# IMU_NoPilot.net
KiCad netlist of a schematic drawn in EAGLE
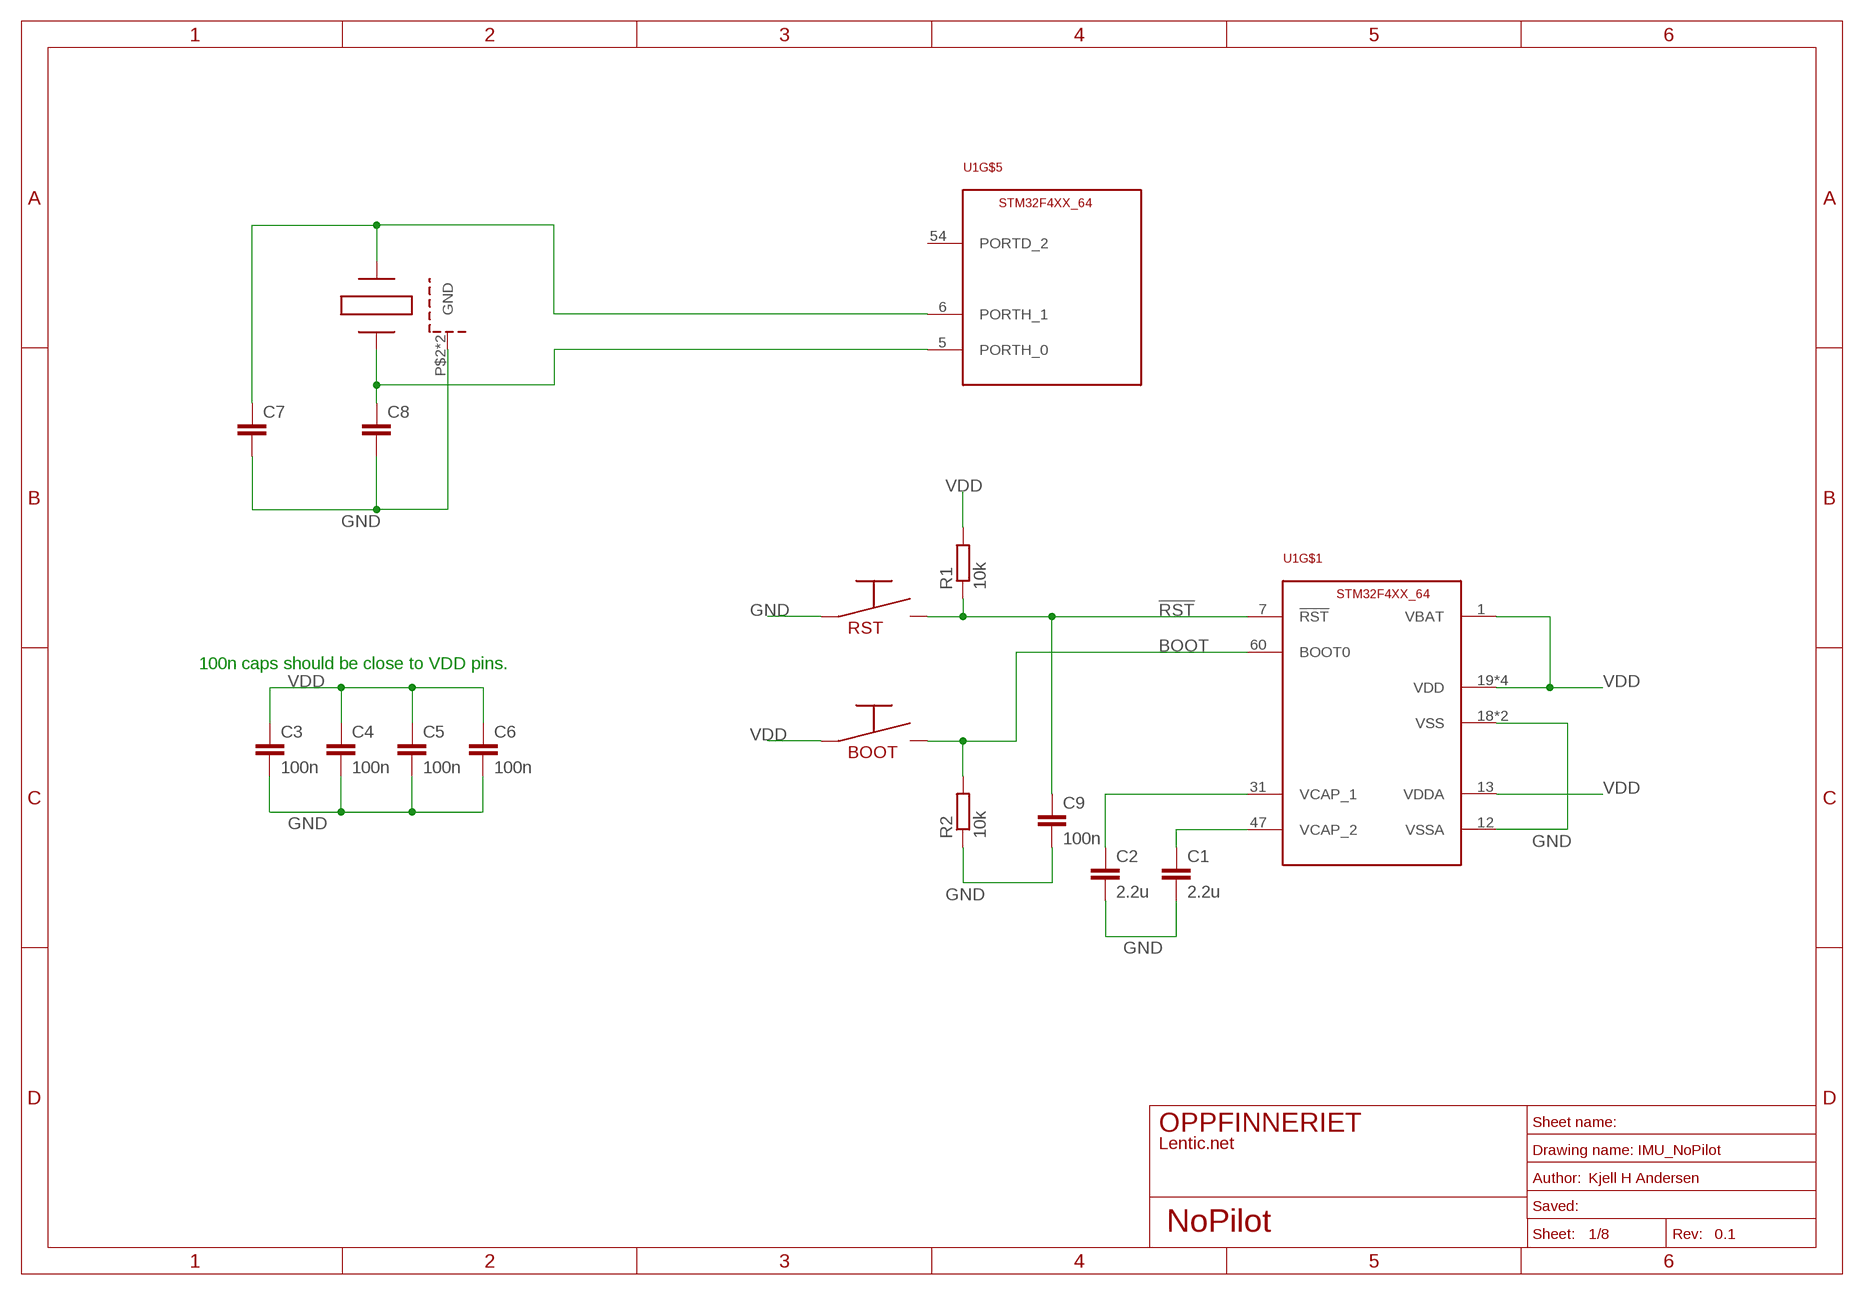
[diagram p0: schematic, sheet 1]
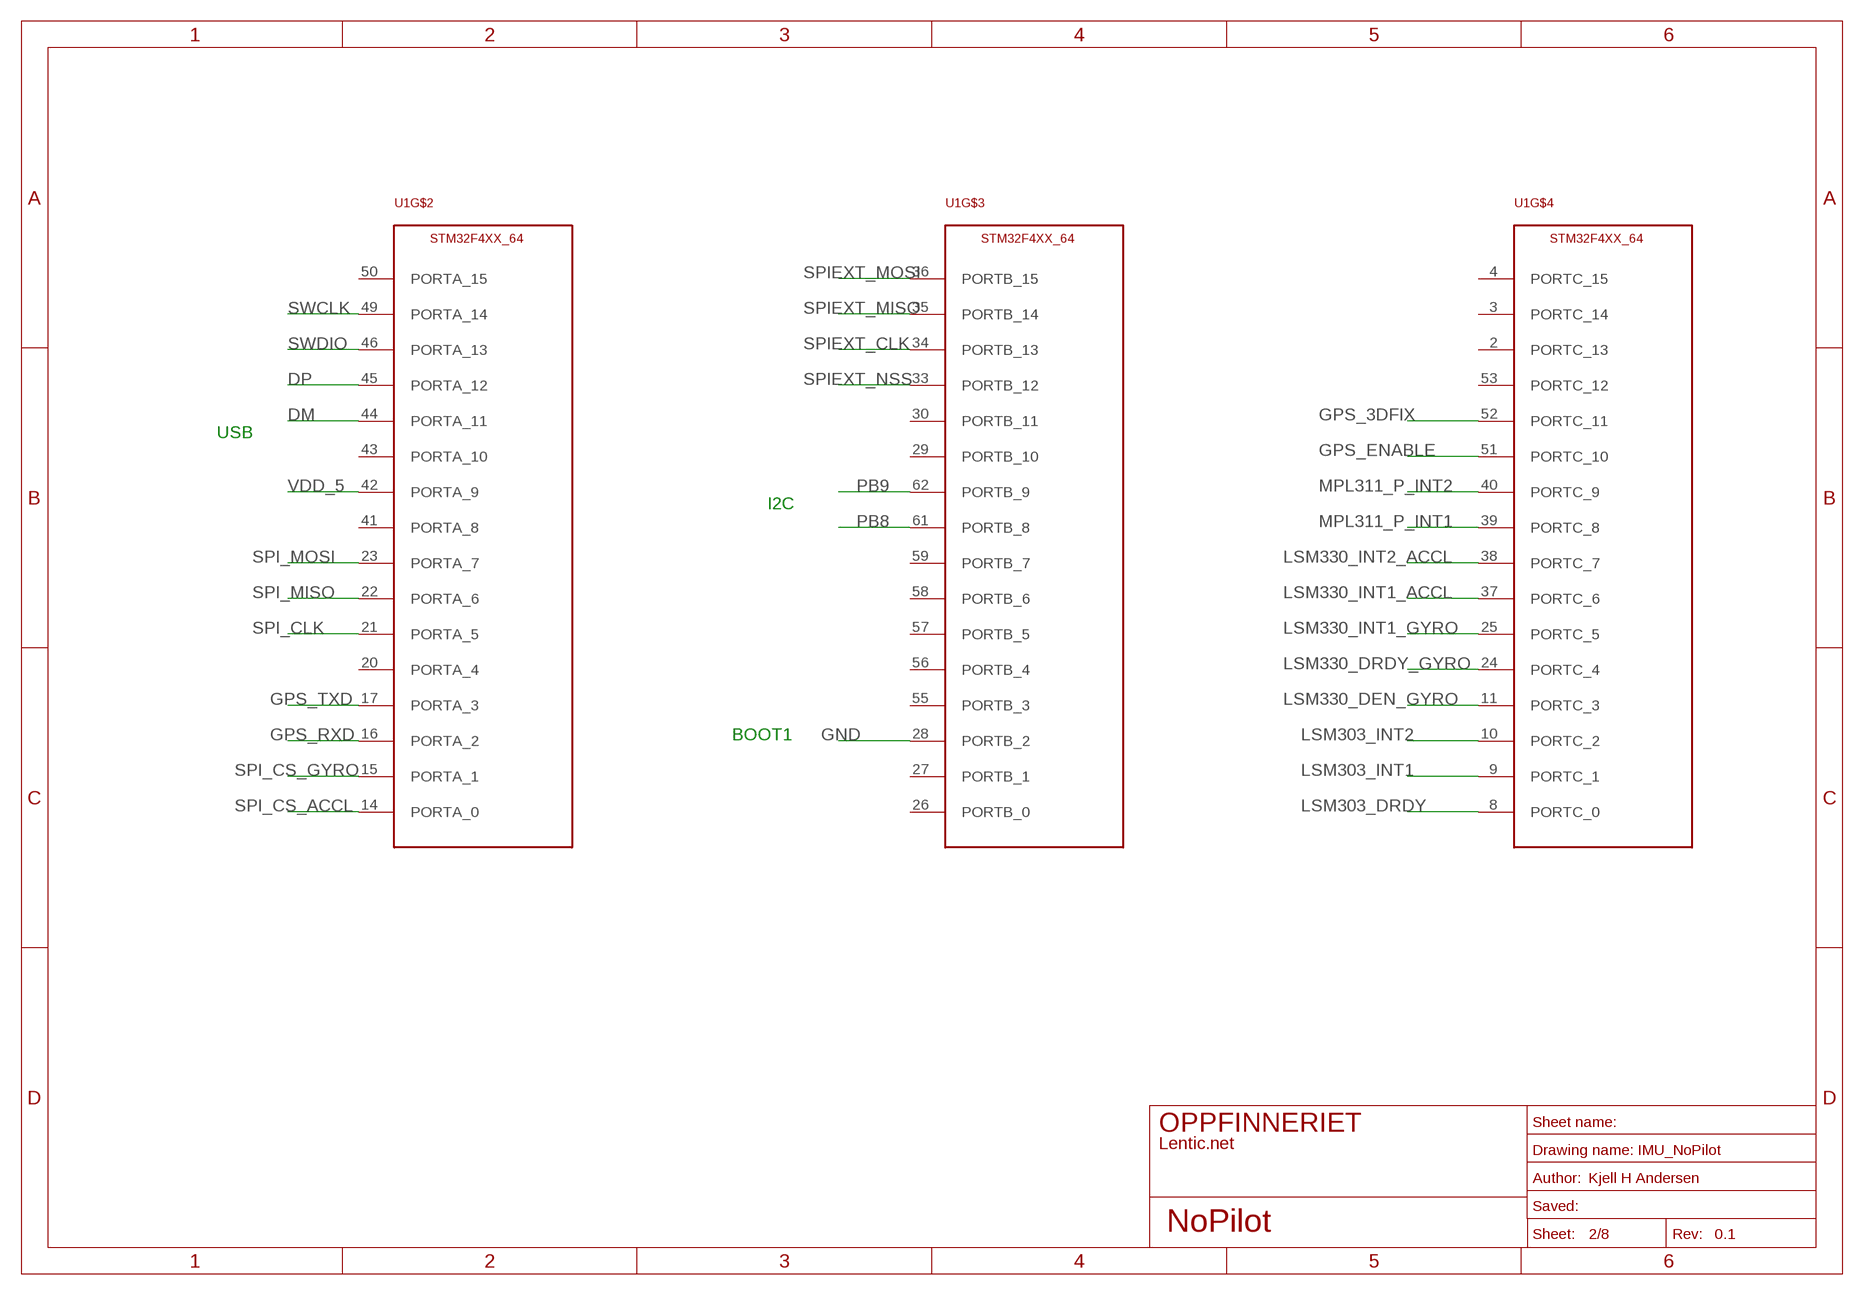
[diagram p1: schematic, sheet 2]
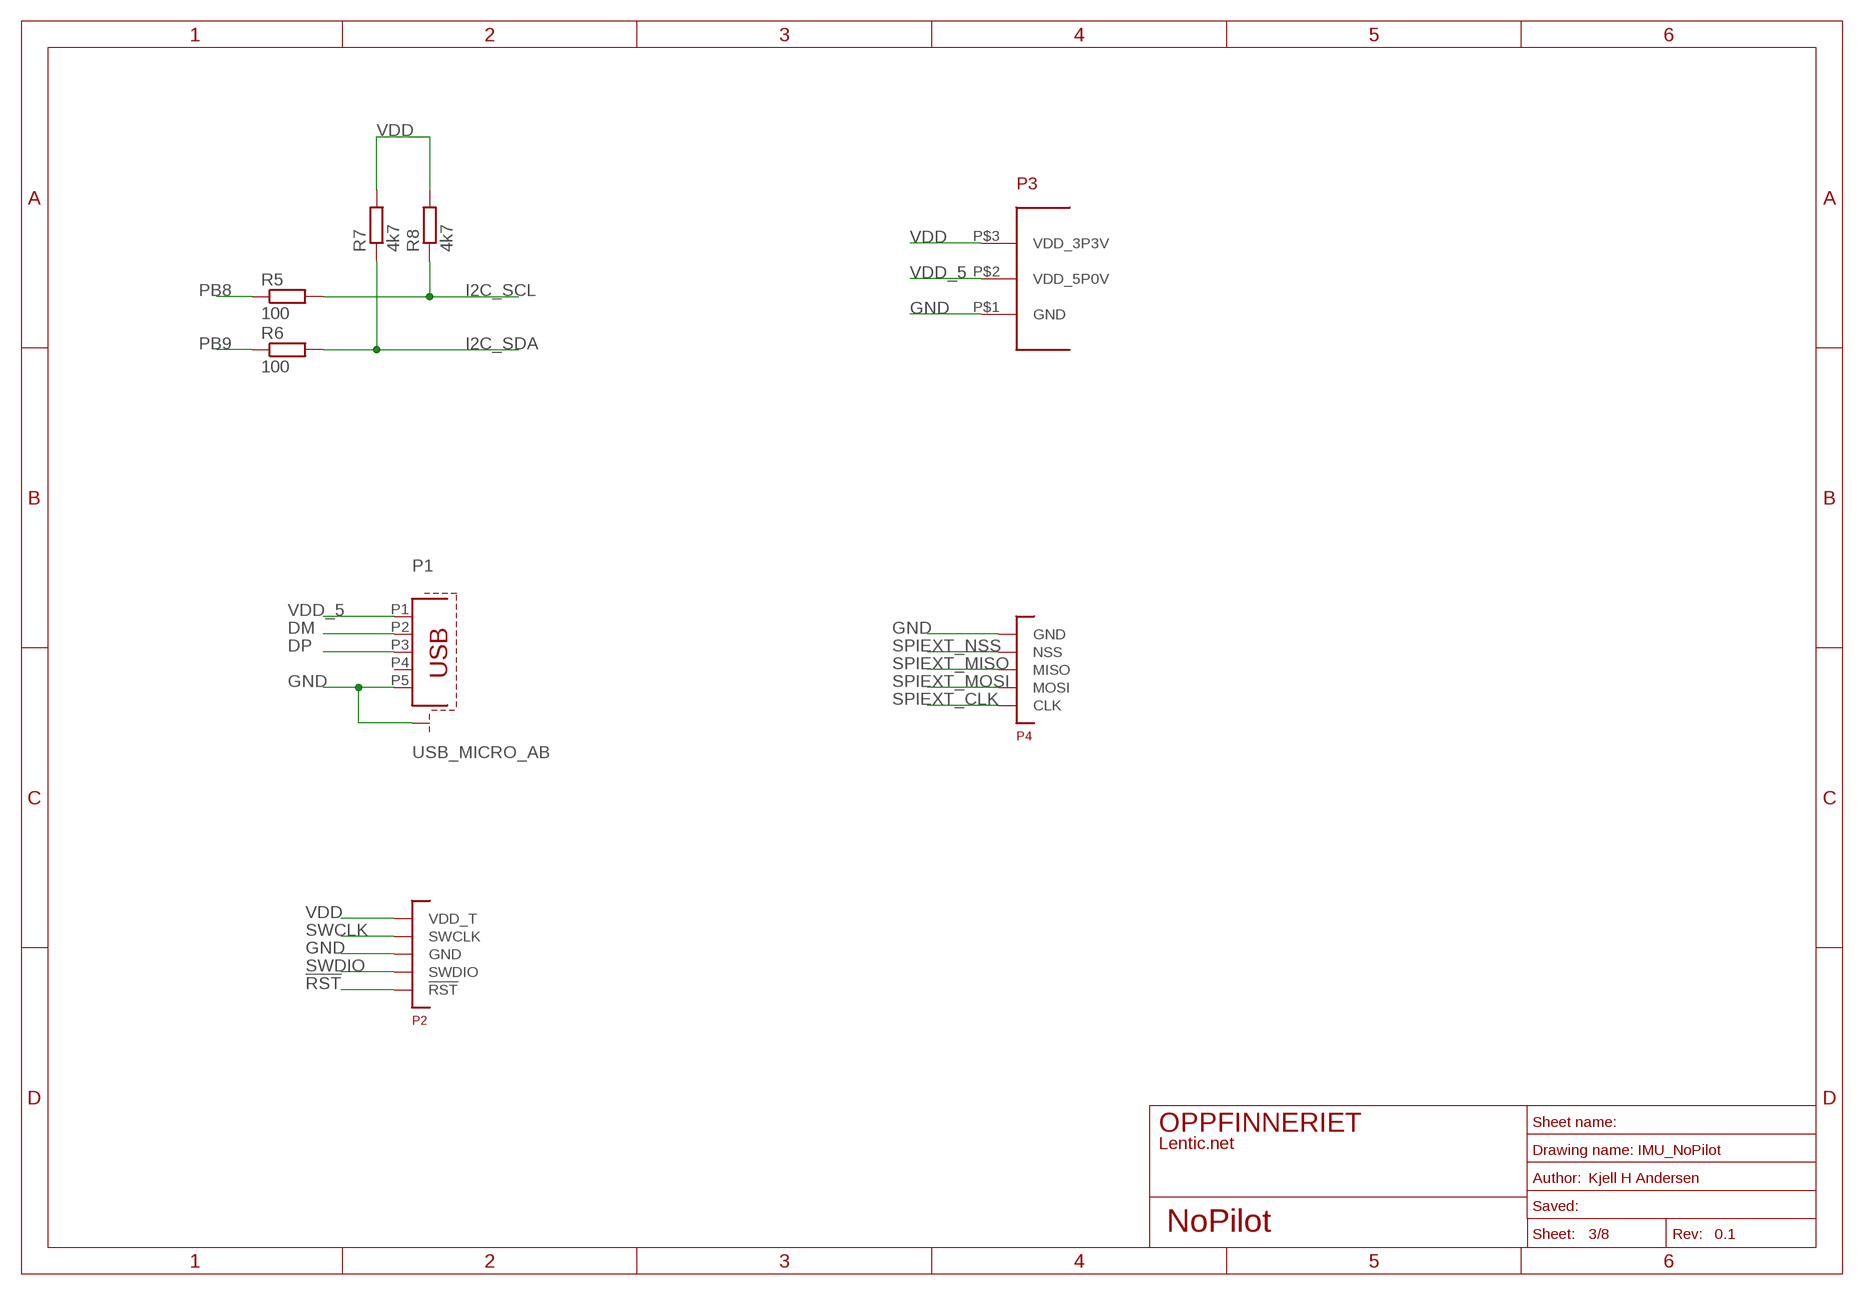
[diagram p2: schematic, sheet 3]
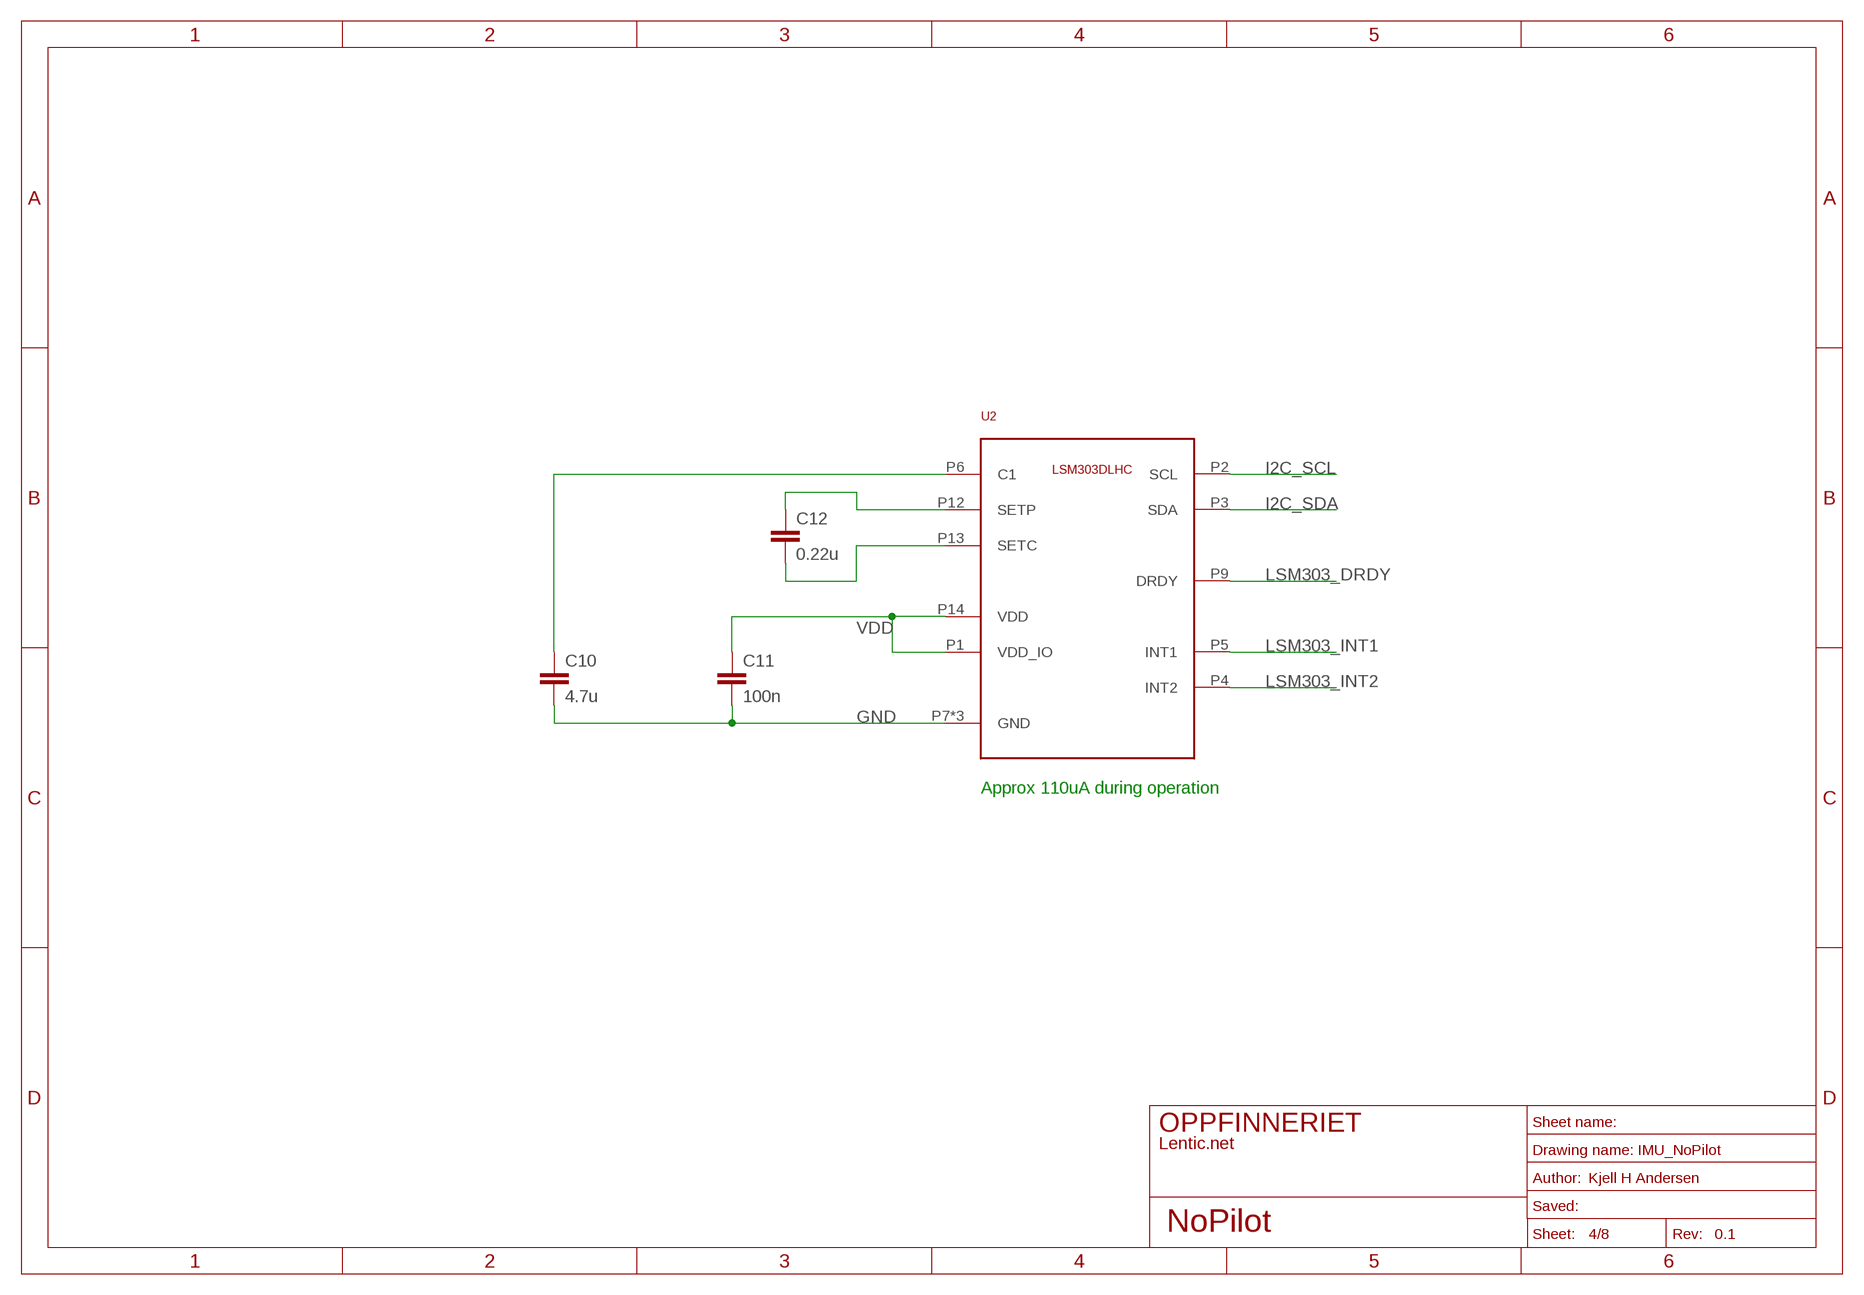
[diagram p3: schematic, sheet 4]
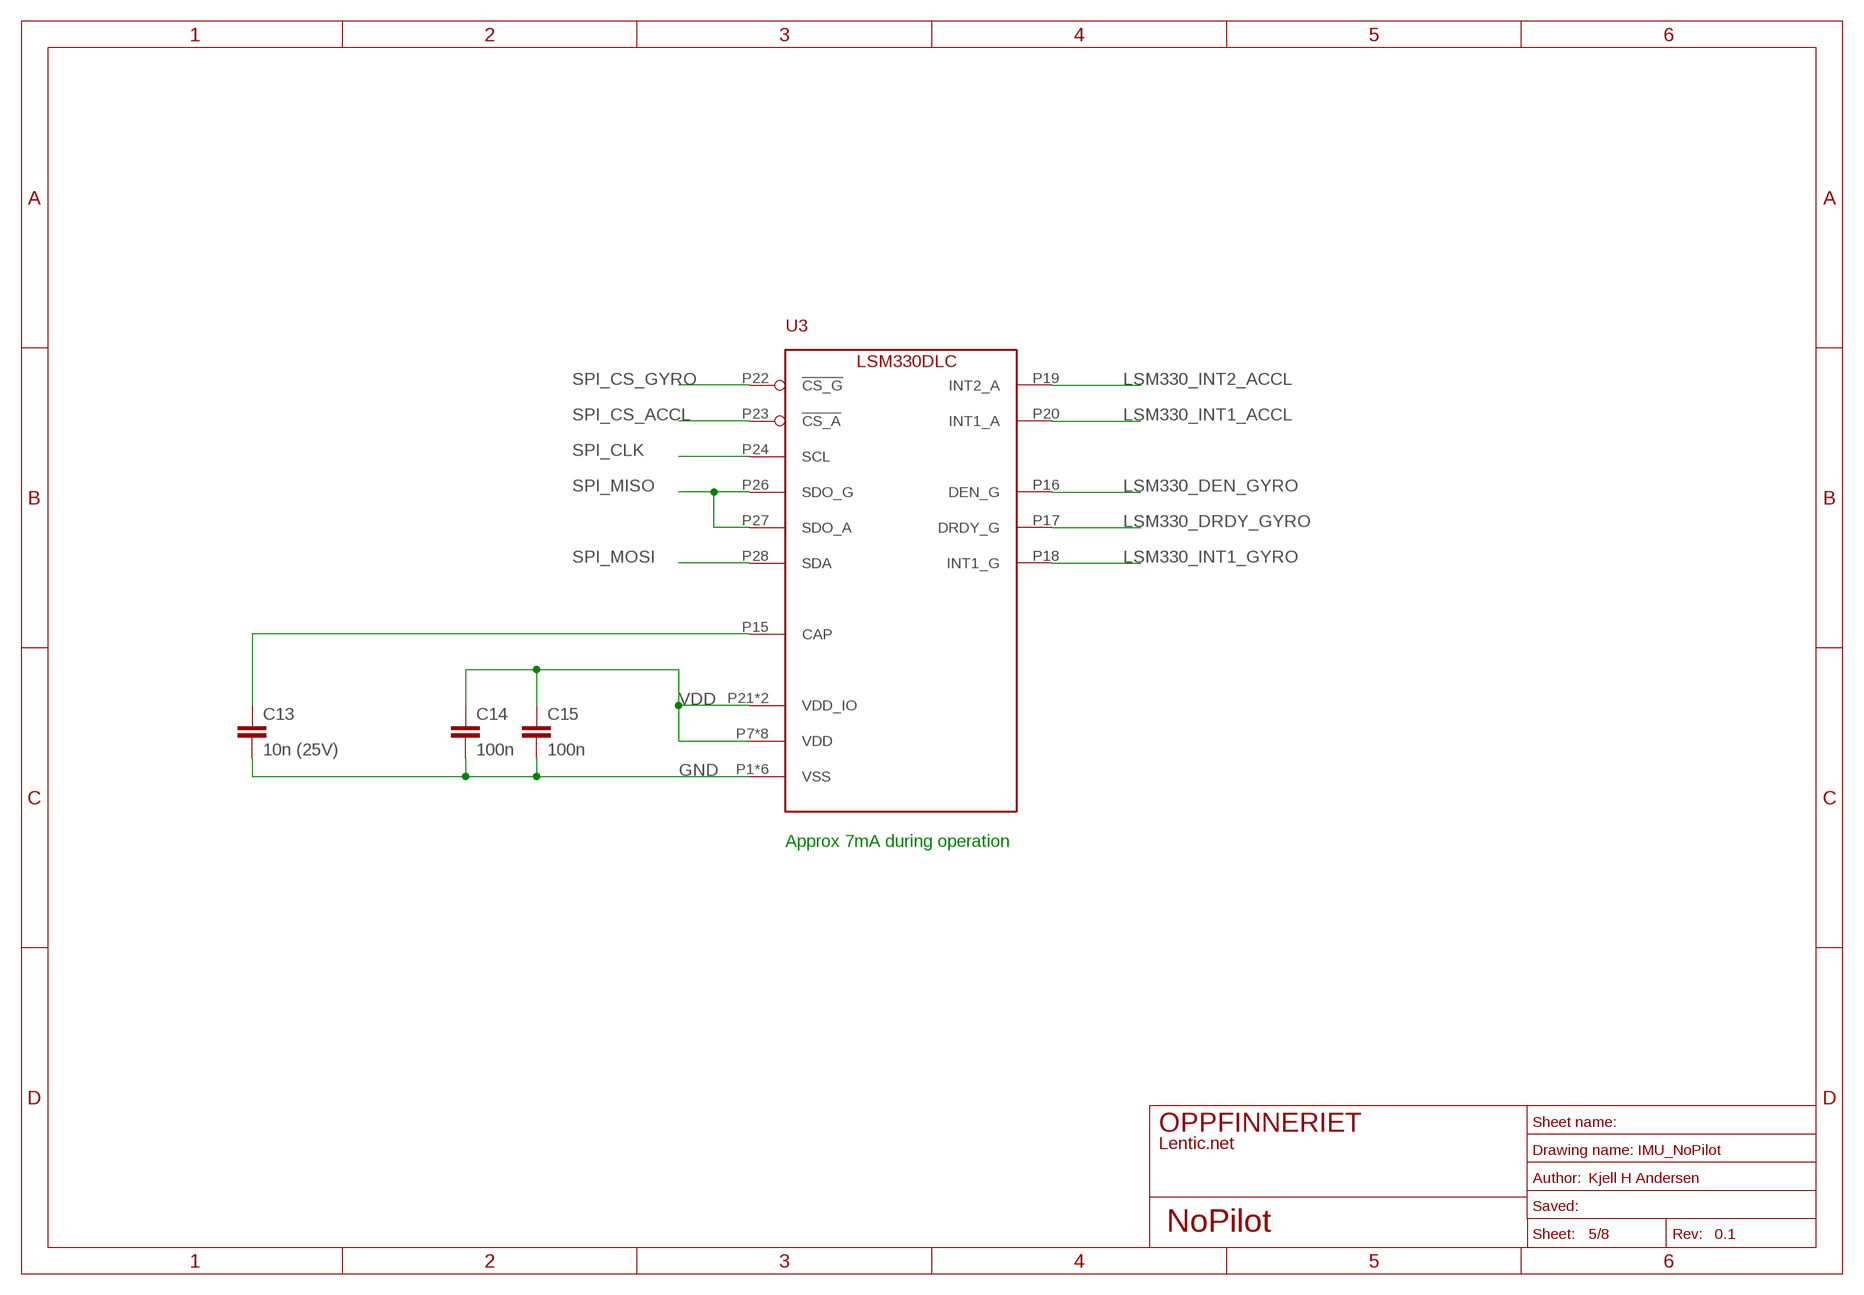
[diagram p4: schematic, sheet 5]
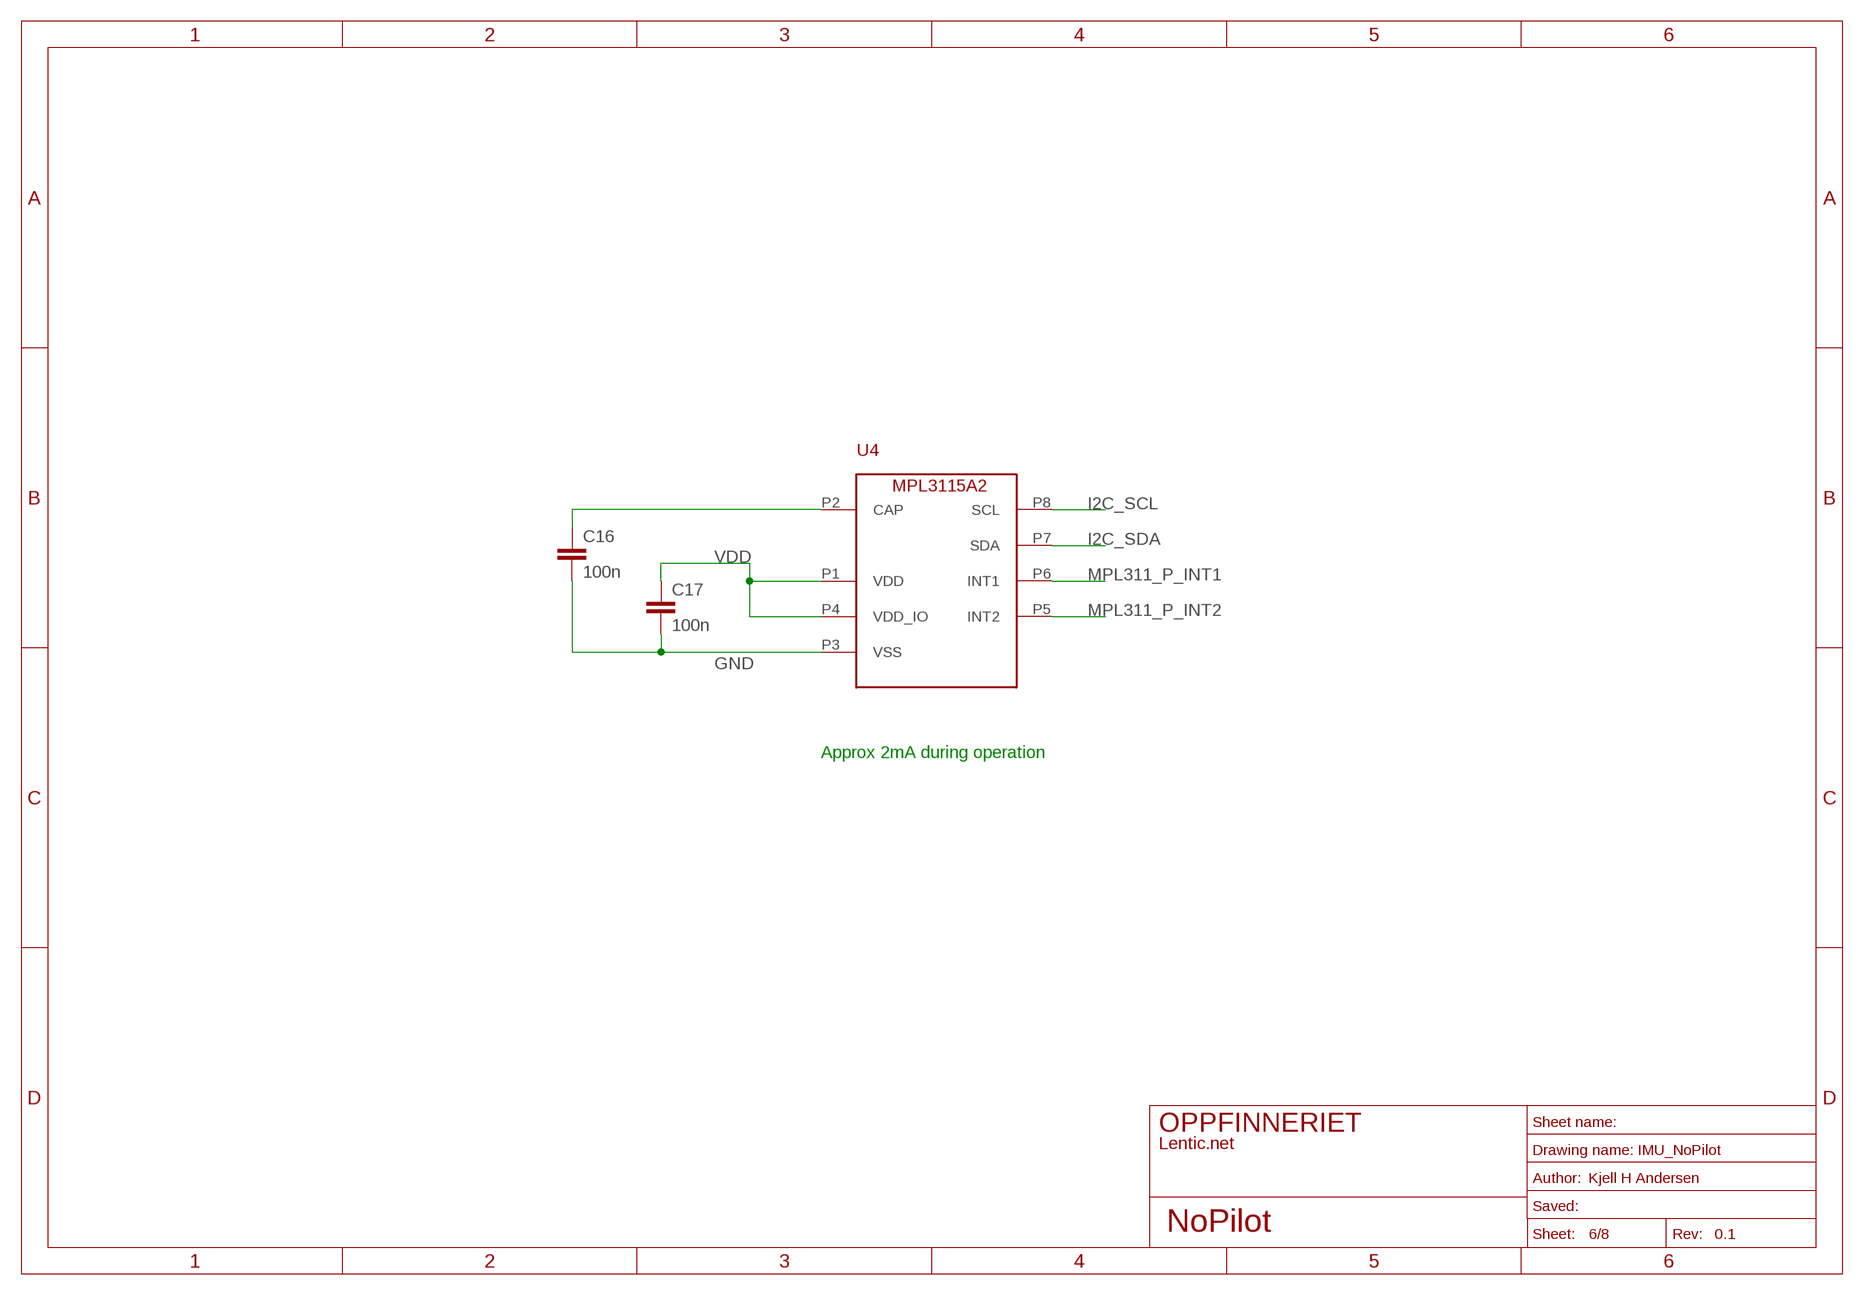
[diagram p5: schematic, sheet 6]
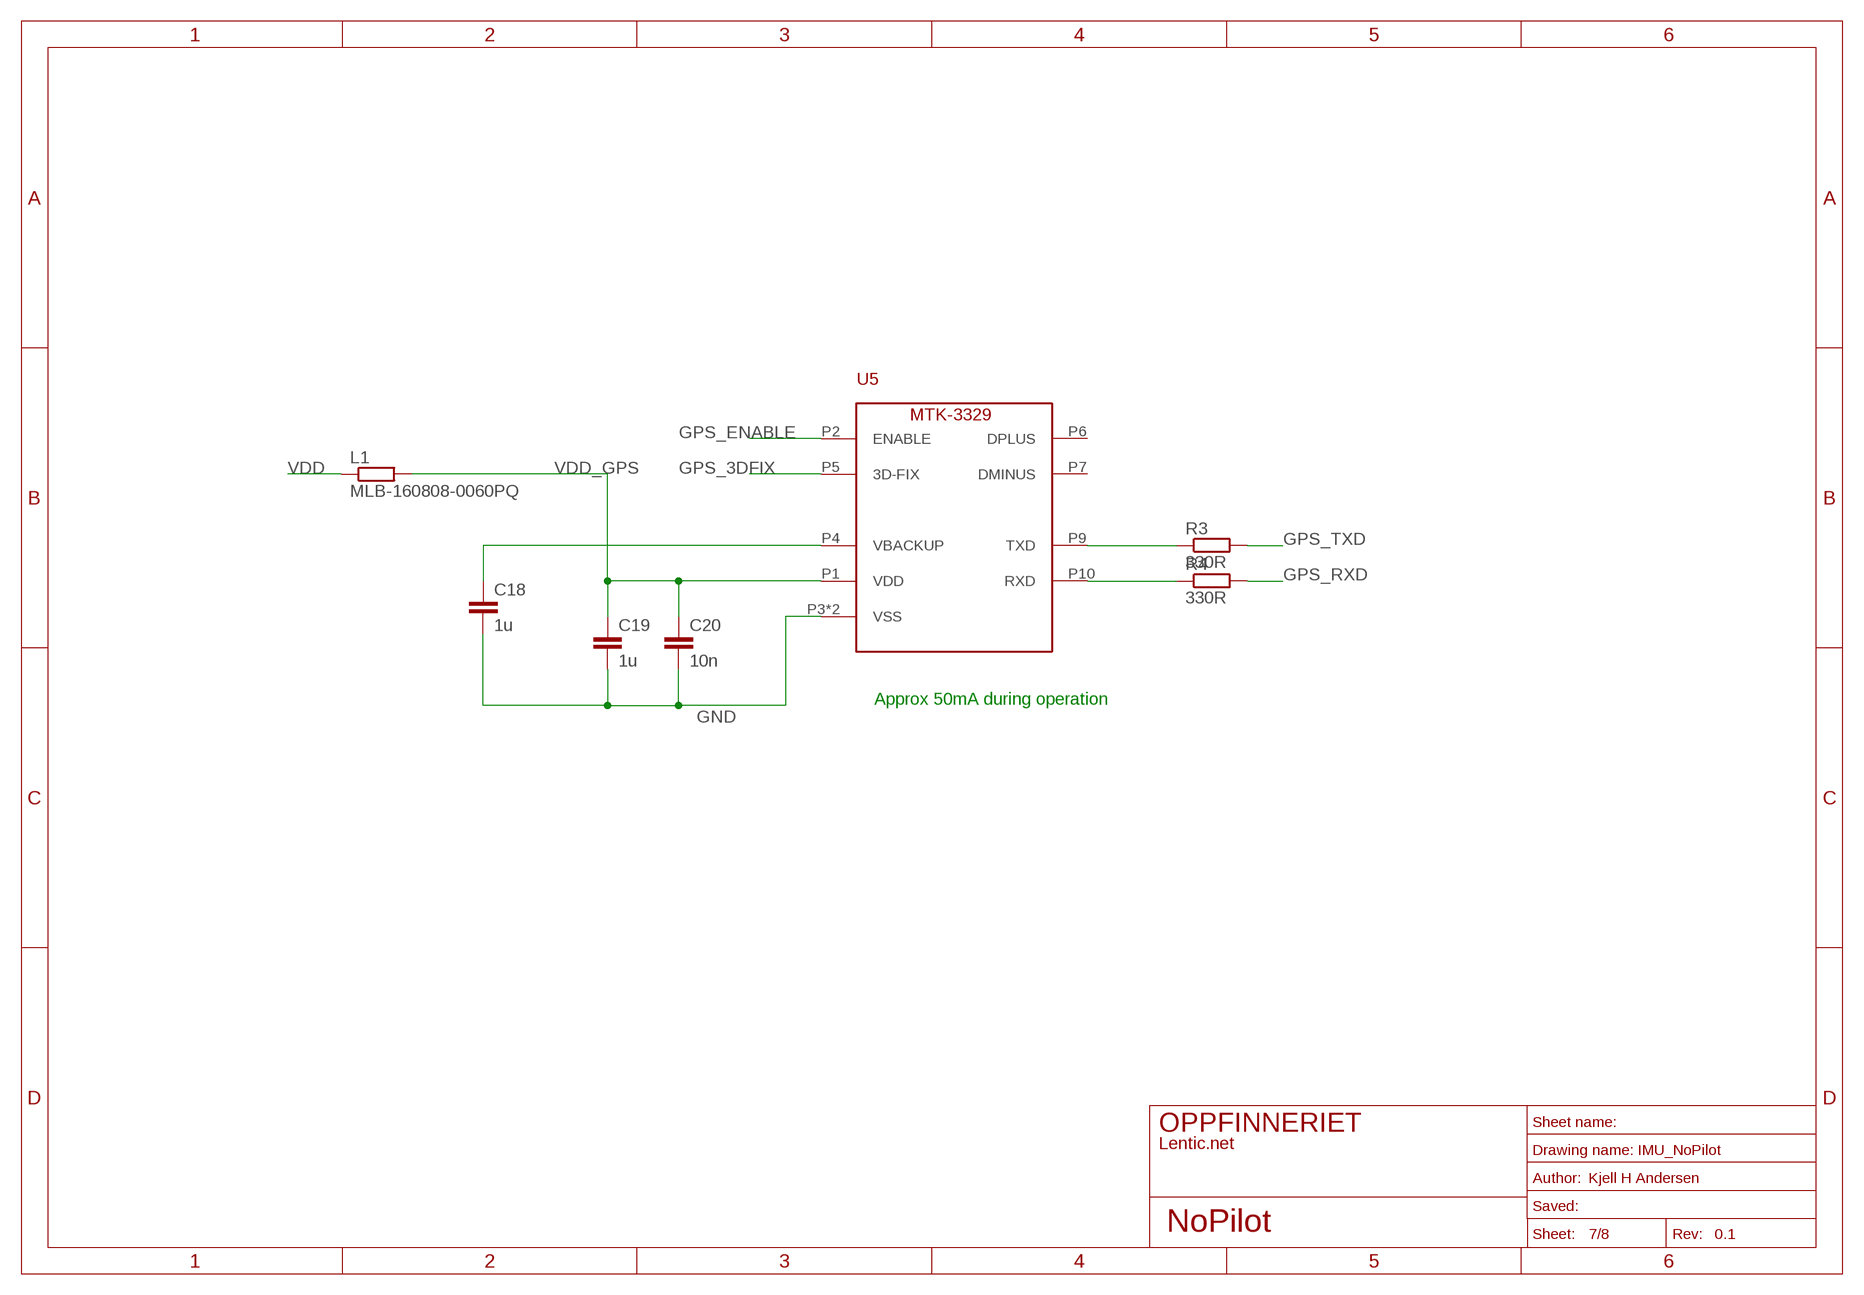
[diagram p6: schematic, sheet 7]
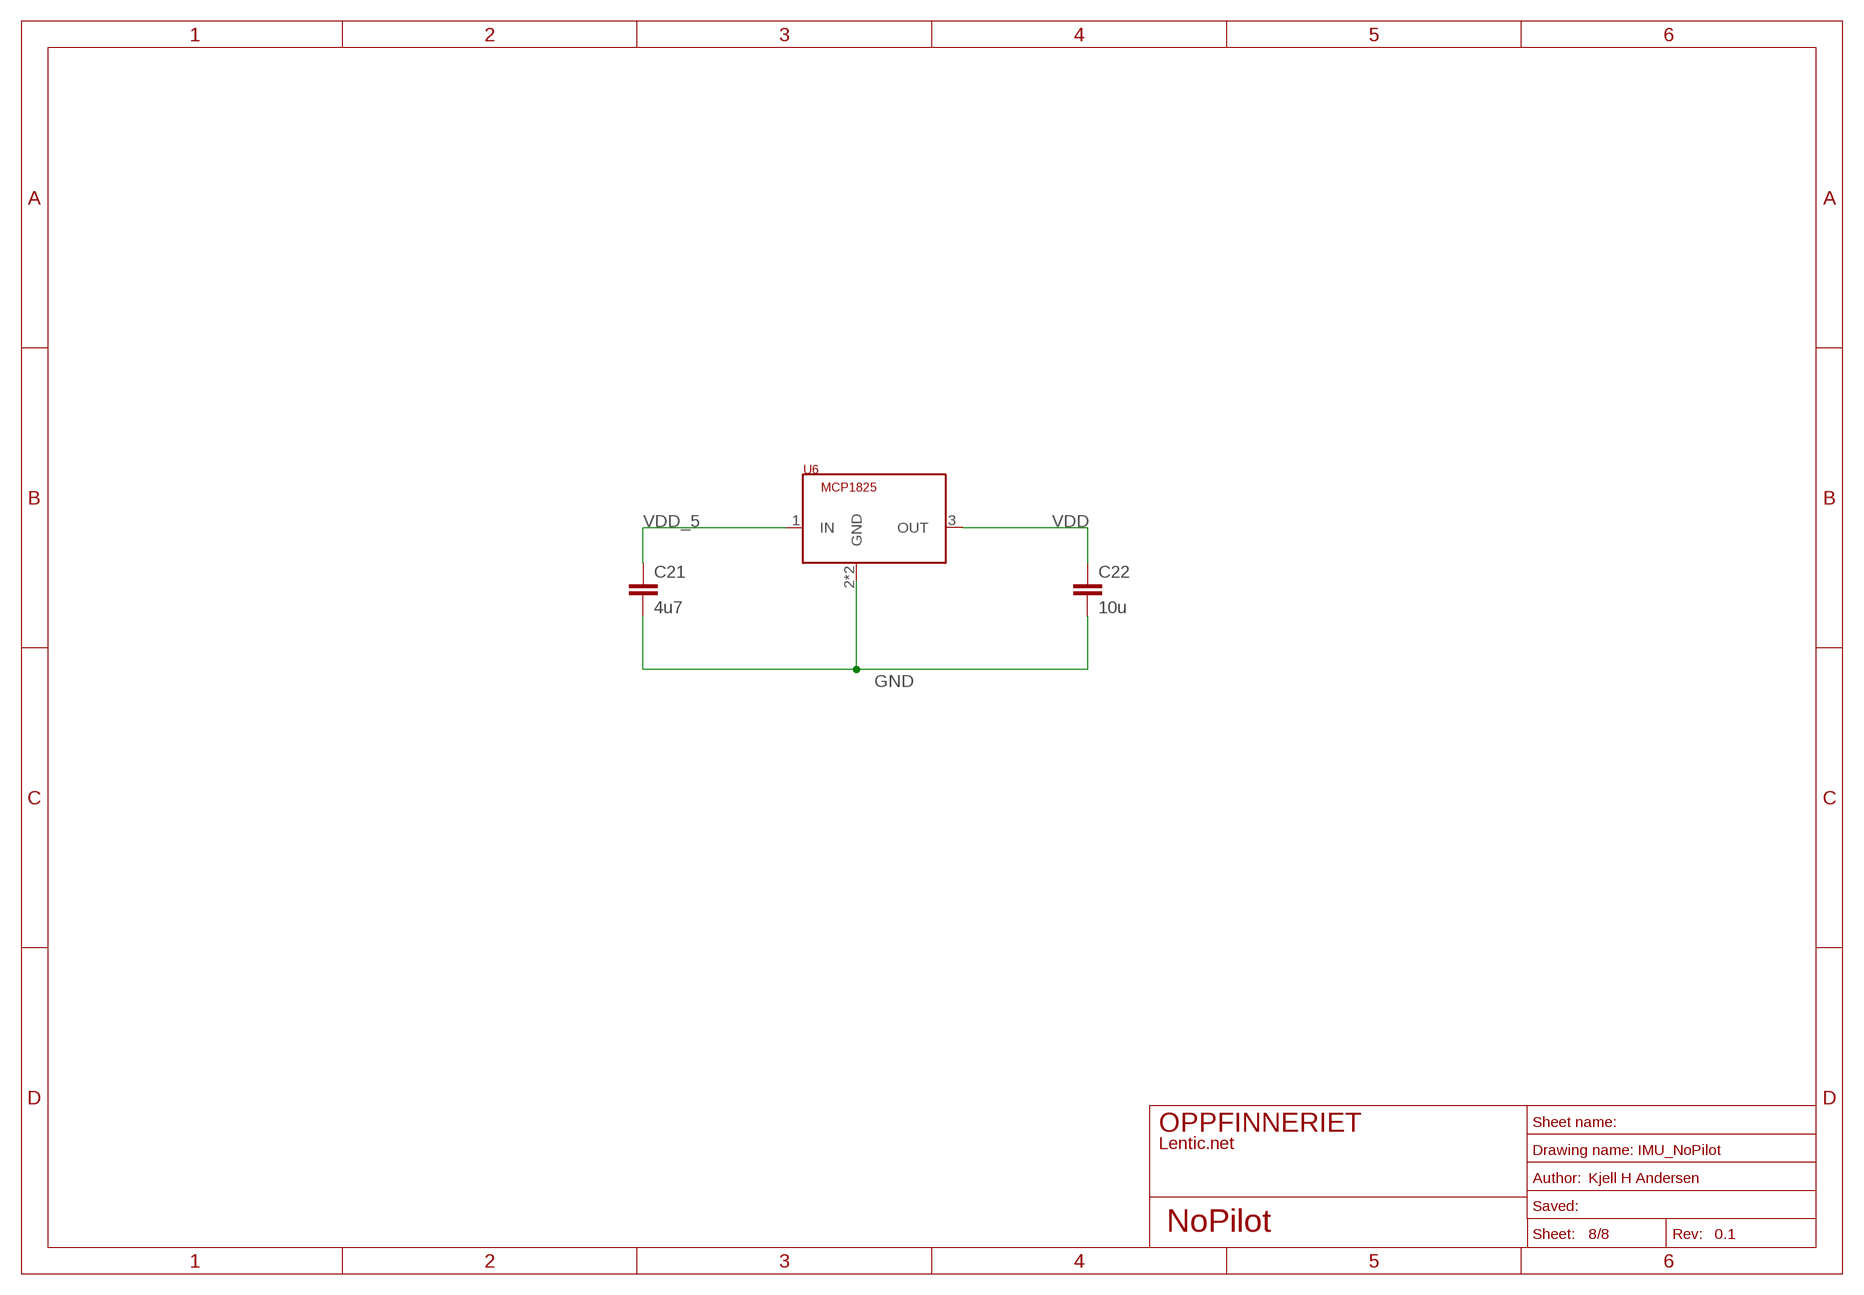
[diagram p7: schematic, sheet 8]

(export (version "E")
  (design (tool "Eeschema 10.0.6"))
  (components
    (comp (ref "C10")
      (value "4.7u")
      (footprint "eagle-import:C0805")
      (libsource (lib "eagle-import") (part "C-EUC0805"))
    )
    (comp (ref "C11")
      (value "100n")
      (footprint "eagle-import:C0402")
      (libsource (lib "eagle-import") (part "C-EUC0402"))
    )
    (comp (ref "C12")
      (value "0.22u")
      (footprint "eagle-import:C0402")
      (libsource (lib "eagle-import") (part "C-EUC0402"))
    )
    (comp (ref "U2")
      (value "LSM303DLHC")
      (footprint "eagle-import:LGA_3X5X1_14L")
      (libsource (lib "eagle-import") (part "LSM303DLHC"))
    )
    (comp (ref "C16")
      (value "100n")
      (footprint "eagle-import:C0402")
      (libsource (lib "eagle-import") (part "C-EUC0402"))
    )
    (comp (ref "C17")
      (value "100n")
      (footprint "eagle-import:C0402")
      (libsource (lib "eagle-import") (part "C-EUC0402"))
    )
    (comp (ref "U4")
      (value "MPL3115A2")
      (footprint "eagle-import:LGA_3X5_8")
      (libsource (lib "eagle-import") (part "MPL3115A2"))
    )
    (comp (ref "C21")
      (value "4u7")
      (footprint "eagle-import:C0805")
      (libsource (lib "eagle-import") (part "C-EUC0805"))
    )
    (comp (ref "C22")
      (value "10u")
      (footprint "eagle-import:C0805")
      (libsource (lib "eagle-import") (part "C-EUC0805"))
    )
    (comp (ref "U6")
      (value "MCP1825")
      (footprint "eagle-import:SOT223")
      (libsource (lib "eagle-import") (part "MCP1825"))
    )
    (comp (ref "P1")
      (value "USB_MICRO_AB")
      (footprint "eagle-import:USB_MICRO_AB")
      (libsource (lib "eagle-import") (part "USB_MICRO_AB"))
    )
    (comp (ref "P2")
      (value "ST_LINK")
      (footprint "eagle-import:ST_LINK")
      (libsource (lib "eagle-import") (part "ST_LINK"))
    )
    (comp (ref "P3")
      (value "PWR3")
      (footprint "eagle-import:PWR3")
      (libsource (lib "eagle-import") (part "PWR3"))
    )
    (comp (ref "P4")
      (value "SPI_EXT")
      (footprint "eagle-import:PINLIST5_2P54")
      (libsource (lib "eagle-import") (part "SPI_EXT"))
    )
    (comp (ref "R5")
      (value "100")
      (footprint "eagle-import:R0402")
      (libsource (lib "eagle-import") (part "R-EU_R0402"))
    )
    (comp (ref "R6")
      (value "100")
      (footprint "eagle-import:R0402")
      (libsource (lib "eagle-import") (part "R-EU_R0402"))
    )
    (comp (ref "R7")
      (value "4k7")
      (footprint "eagle-import:R0402")
      (libsource (lib "eagle-import") (part "R-EU_R0402"))
    )
    (comp (ref "R8")
      (value "4k7")
      (footprint "eagle-import:R0402")
      (libsource (lib "eagle-import") (part "R-EU_R0402"))
    )
    (comp (ref "C18")
      (value "1u")
      (footprint "eagle-import:C0805")
      (libsource (lib "eagle-import") (part "C-EUC0805"))
    )
    (comp (ref "C19")
      (value "1u")
      (footprint "eagle-import:C0805")
      (libsource (lib "eagle-import") (part "C-EUC0805"))
    )
    (comp (ref "C20")
      (value "10n")
      (footprint "eagle-import:C0402")
      (libsource (lib "eagle-import") (part "C-EUC0402"))
    )
    (comp (ref "L1")
      (value "MLB-160808-0060PQ")
      (footprint "eagle-import:R0603")
      (libsource (lib "eagle-import") (part "R-EU_R0603"))
    )
    (comp (ref "R3")
      (value "330R")
      (footprint "eagle-import:R0402")
      (libsource (lib "eagle-import") (part "R-EU_R0402"))
    )
    (comp (ref "R4")
      (value "330R")
      (footprint "eagle-import:R0402")
      (libsource (lib "eagle-import") (part "R-EU_R0402"))
    )
    (comp (ref "U5")
      (value "MTK-3329")
      (footprint "eagle-import:MTK-3329")
      (libsource (lib "eagle-import") (part "MTK-3329"))
    )
    (comp (ref "BOOT")
      (value "OMRON_B3FS_1000")
      (footprint "eagle-import:OMROM_B3FS-1XXX")
      (libsource (lib "eagle-import") (part "OMRON_B3FS_1000"))
    )
    (comp (ref "C1")
      (value "2.2u")
      (footprint "eagle-import:C0805")
      (libsource (lib "eagle-import") (part "C-EUC0805"))
    )
    (comp (ref "C2")
      (value "2.2u")
      (footprint "eagle-import:C0805")
      (libsource (lib "eagle-import") (part "C-EUC0805"))
    )
    (comp (ref "C3")
      (value "100n")
      (footprint "eagle-import:C0402")
      (libsource (lib "eagle-import") (part "C-EUC0402"))
    )
    (comp (ref "C4")
      (value "100n")
      (footprint "eagle-import:C0402")
      (libsource (lib "eagle-import") (part "C-EUC0402"))
    )
    (comp (ref "C5")
      (value "100n")
      (footprint "eagle-import:C0402")
      (libsource (lib "eagle-import") (part "C-EUC0402"))
    )
    (comp (ref "C6")
      (value "100n")
      (footprint "eagle-import:C0402")
      (libsource (lib "eagle-import") (part "C-EUC0402"))
    )
    (comp (ref "C7")
      (value "C-EUC0402")
      (footprint "eagle-import:C0402")
      (libsource (lib "eagle-import") (part "C-EUC0402"))
    )
    (comp (ref "C8")
      (value "C-EUC0402")
      (footprint "eagle-import:C0402")
      (libsource (lib "eagle-import") (part "C-EUC0402"))
    )
    (comp (ref "C9")
      (value "100n")
      (footprint "eagle-import:C0402")
      (libsource (lib "eagle-import") (part "C-EUC0402"))
    )
    (comp (ref "R1")
      (value "10k")
      (footprint "eagle-import:R0402")
      (libsource (lib "eagle-import") (part "R-EU_R0402"))
    )
    (comp (ref "R2")
      (value "10k")
      (footprint "eagle-import:R0402")
      (libsource (lib "eagle-import") (part "R-EU_R0402"))
    )
    (comp (ref "RST")
      (value "OMRON_B3FS_1000")
      (footprint "eagle-import:OMROM_B3FS-1XXX")
      (libsource (lib "eagle-import") (part "OMRON_B3FS_1000"))
    )
    (comp (ref "U1")
      (value "STM32F4XX_64")
      (footprint "eagle-import:TQFP64")
      (libsource (lib "eagle-import") (part "STM32F4XX_64"))
    )
    (comp (ref "XTAL1")
      (value "XTAL_5X3P2")
      (footprint "eagle-import:XTAL_5X3P2")
      (libsource (lib "eagle-import") (part "XTAL_5X3P2"))
    )
    (comp (ref "C13")
      (value "10n (25V)")
      (footprint "eagle-import:C0402")
      (libsource (lib "eagle-import") (part "C-EUC0402"))
    )
    (comp (ref "C14")
      (value "100n")
      (footprint "eagle-import:C0402")
      (libsource (lib "eagle-import") (part "C-EUC0402"))
    )
    (comp (ref "C15")
      (value "100n")
      (footprint "eagle-import:C0402")
      (libsource (lib "eagle-import") (part "C-EUC0402"))
    )
    (comp (ref "U3")
      (value "LSM330DLC")
      (footprint "eagle-import:LGA_4X5X1P1_28L")
      (libsource (lib "eagle-import") (part "LSM330DLC"))
    )
  )
  (nets
    (net (code "1") (name "BOOT") (class "Default")
      (node (ref "BOOT") (pin "P3") (pinfunction "P$2_P3") (pintype "bidirectional"))
      (node (ref "BOOT") (pin "P4") (pinfunction "P$2_P4") (pintype "bidirectional"))
      (node (ref "R2") (pin "2") (pinfunction "2_2") (pintype "passive"))
      (node (ref "U1") (pin "60") (pinfunction "BOOT0_60") (pintype "bidirectional"))
    )
    (net (code "2") (name "DM") (class "Default")
      (node (ref "P1") (pin "P2") (pinfunction "2_P2") (pintype "passive"))
      (node (ref "U1") (pin "44") (pinfunction "PORTA_11_44") (pintype "bidirectional"))
    )
    (net (code "3") (name "DP") (class "Default")
      (node (ref "P1") (pin "P3") (pinfunction "3_P3") (pintype "passive"))
      (node (ref "U1") (pin "45") (pinfunction "PORTA_12_45") (pintype "bidirectional"))
    )
    (net (code "4") (name "GND") (class "Default")
      (node (ref "C1") (pin "2") (pinfunction "2_2") (pintype "passive"))
      (node (ref "C10") (pin "2") (pinfunction "2_2") (pintype "passive"))
      (node (ref "C11") (pin "2") (pinfunction "2_2") (pintype "passive"))
      (node (ref "C13") (pin "2") (pinfunction "2_2") (pintype "passive"))
      (node (ref "C14") (pin "2") (pinfunction "2_2") (pintype "passive"))
      (node (ref "C15") (pin "2") (pinfunction "2_2") (pintype "passive"))
      (node (ref "C16") (pin "2") (pinfunction "2_2") (pintype "passive"))
      (node (ref "C17") (pin "2") (pinfunction "2_2") (pintype "passive"))
      (node (ref "C18") (pin "2") (pinfunction "2_2") (pintype "passive"))
      (node (ref "C19") (pin "2") (pinfunction "2_2") (pintype "passive"))
      (node (ref "C2") (pin "2") (pinfunction "2_2") (pintype "passive"))
      (node (ref "C20") (pin "2") (pinfunction "2_2") (pintype "passive"))
      (node (ref "C21") (pin "2") (pinfunction "2_2") (pintype "passive"))
      (node (ref "C22") (pin "2") (pinfunction "2_2") (pintype "passive"))
      (node (ref "C3") (pin "2") (pinfunction "2_2") (pintype "passive"))
      (node (ref "C4") (pin "2") (pinfunction "2_2") (pintype "passive"))
      (node (ref "C5") (pin "2") (pinfunction "2_2") (pintype "passive"))
      (node (ref "C6") (pin "2") (pinfunction "2_2") (pintype "passive"))
      (node (ref "C7") (pin "2") (pinfunction "2_2") (pintype "passive"))
      (node (ref "C8") (pin "2") (pinfunction "2_2") (pintype "passive"))
      (node (ref "C9") (pin "2") (pinfunction "2_2") (pintype "passive"))
      (node (ref "P1") (pin "NC1") (pinfunction "S1_NC1") (pintype "passive"))
      (node (ref "P1") (pin "NC2") (pinfunction "S1_NC2") (pintype "passive"))
      (node (ref "P1") (pin "NC3") (pinfunction "S1_NC3") (pintype "passive"))
      (node (ref "P1") (pin "NC4") (pinfunction "S1_NC4") (pintype "passive"))
      (node (ref "P1") (pin "NC5") (pinfunction "S1_NC5") (pintype "passive"))
      (node (ref "P1") (pin "NC6") (pinfunction "S1_NC6") (pintype "passive"))
      (node (ref "P1") (pin "P5") (pinfunction "5_P5") (pintype "passive"))
      (node (ref "P2") (pin "P$3") (pinfunction "GND_P$3") (pintype "bidirectional"))
      (node (ref "P3") (pin "P$1") (pinfunction "GND_P$1") (pintype "bidirectional"))
      (node (ref "P4") (pin "P$5") (pinfunction "GND_P$5") (pintype "bidirectional"))
      (node (ref "R2") (pin "1") (pinfunction "1_1") (pintype "passive"))
      (node (ref "RST") (pin "P1") (pinfunction "P$1_P1") (pintype "bidirectional"))
      (node (ref "RST") (pin "P2") (pinfunction "P$1_P2") (pintype "bidirectional"))
      (node (ref "U1") (pin "12") (pinfunction "VSSA_12") (pintype "bidirectional"))
      (node (ref "U1") (pin "18") (pinfunction "VSS_18") (pintype "bidirectional"))
      (node (ref "U1") (pin "28") (pinfunction "PORTB_2_28") (pintype "bidirectional"))
      (node (ref "U1") (pin "63") (pinfunction "VSS_63") (pintype "bidirectional"))
      (node (ref "U2") (pin "P10") (pinfunction "GND_P10") (pintype "bidirectional"))
      (node (ref "U2") (pin "P11") (pinfunction "GND_P11") (pintype "bidirectional"))
      (node (ref "U2") (pin "P7") (pinfunction "GND_P7") (pintype "bidirectional"))
      (node (ref "U3") (pin "P1") (pinfunction "VSS_P1") (pintype "power_in"))
      (node (ref "U3") (pin "P2") (pinfunction "VSS_P2") (pintype "power_in"))
      (node (ref "U3") (pin "P3") (pinfunction "VSS_P3") (pintype "power_in"))
      (node (ref "U3") (pin "P4") (pinfunction "VSS_P4") (pintype "power_in"))
      (node (ref "U3") (pin "P5") (pinfunction "VSS_P5") (pintype "power_in"))
      (node (ref "U3") (pin "P6") (pinfunction "VSS_P6") (pintype "power_in"))
      (node (ref "U4") (pin "P3") (pinfunction "VSS_P3") (pintype "power_in"))
      (node (ref "U5") (pin "P3") (pinfunction "VSS_P3") (pintype "bidirectional"))
      (node (ref "U5") (pin "P8") (pinfunction "VSS_P8") (pintype "bidirectional"))
      (node (ref "U6") (pin "2") (pinfunction "GND_2") (pintype "bidirectional"))
      (node (ref "U6") (pin "4") (pinfunction "GND_4") (pintype "bidirectional"))
      (node (ref "XTAL1") (pin "P$2") (pinfunction "GND_P$2") (pintype "bidirectional"))
      (node (ref "XTAL1") (pin "P$4") (pinfunction "GND_P$4") (pintype "bidirectional"))
    )
    (net (code "5") (name "GPS_3DFIX") (class "Default")
      (node (ref "U1") (pin "52") (pinfunction "PORTC_11_52") (pintype "bidirectional"))
      (node (ref "U5") (pin "P5") (pinfunction "3D-FIX_P5") (pintype "bidirectional"))
    )
    (net (code "6") (name "GPS_ENABLE") (class "Default")
      (node (ref "U1") (pin "51") (pinfunction "PORTC_10_51") (pintype "bidirectional"))
      (node (ref "U5") (pin "P2") (pinfunction "ENABLE_P2") (pintype "bidirectional"))
    )
    (net (code "7") (name "GPS_RXD") (class "Default")
      (node (ref "R4") (pin "2") (pinfunction "2_2") (pintype "passive"))
      (node (ref "U1") (pin "16") (pinfunction "PORTA_2_16") (pintype "bidirectional"))
    )
    (net (code "8") (name "GPS_TXD") (class "Default")
      (node (ref "R3") (pin "2") (pinfunction "2_2") (pintype "passive"))
      (node (ref "U1") (pin "17") (pinfunction "PORTA_3_17") (pintype "bidirectional"))
    )
    (net (code "9") (name "I2C_SCL") (class "Default")
      (node (ref "R5") (pin "2") (pinfunction "2_2") (pintype "passive"))
      (node (ref "R8") (pin "1") (pinfunction "1_1") (pintype "passive"))
      (node (ref "U2") (pin "P2") (pinfunction "SCL_P2") (pintype "bidirectional"))
      (node (ref "U4") (pin "P8") (pinfunction "SCL_P8") (pintype "input"))
    )
    (net (code "10") (name "I2C_SDA") (class "Default")
      (node (ref "R6") (pin "2") (pinfunction "2_2") (pintype "passive"))
      (node (ref "R7") (pin "1") (pinfunction "1_1") (pintype "passive"))
      (node (ref "U2") (pin "P3") (pinfunction "SDA_P3") (pintype "bidirectional"))
      (node (ref "U4") (pin "P7") (pinfunction "SDA_P7") (pintype "bidirectional"))
    )
    (net (code "11") (name "LSM303_DRDY") (class "Default")
      (node (ref "U1") (pin "8") (pinfunction "PORTC_0_8") (pintype "bidirectional"))
      (node (ref "U2") (pin "P9") (pinfunction "DRDY_P9") (pintype "bidirectional"))
    )
    (net (code "12") (name "LSM303_INT1") (class "Default")
      (node (ref "U1") (pin "9") (pinfunction "PORTC_1_9") (pintype "bidirectional"))
      (node (ref "U2") (pin "P5") (pinfunction "INT1_P5") (pintype "bidirectional"))
    )
    (net (code "13") (name "LSM303_INT2") (class "Default")
      (node (ref "U1") (pin "10") (pinfunction "PORTC_2_10") (pintype "bidirectional"))
      (node (ref "U2") (pin "P4") (pinfunction "INT2_P4") (pintype "bidirectional"))
    )
    (net (code "14") (name "LSM330_DEN_GYRO") (class "Default")
      (node (ref "U1") (pin "11") (pinfunction "PORTC_3_11") (pintype "bidirectional"))
      (node (ref "U3") (pin "P16") (pinfunction "DEN_G_P16") (pintype "input"))
    )
    (net (code "15") (name "LSM330_DRDY_GYRO") (class "Default")
      (node (ref "U1") (pin "24") (pinfunction "PORTC_4_24") (pintype "bidirectional"))
      (node (ref "U3") (pin "P17") (pinfunction "DRDY_G_P17") (pintype "output"))
    )
    (net (code "16") (name "LSM330_INT1_ACCL") (class "Default")
      (node (ref "U1") (pin "37") (pinfunction "PORTC_6_37") (pintype "bidirectional"))
      (node (ref "U3") (pin "P20") (pinfunction "INT1_A_P20") (pintype "output"))
    )
    (net (code "17") (name "LSM330_INT1_GYRO") (class "Default")
      (node (ref "U1") (pin "25") (pinfunction "PORTC_5_25") (pintype "bidirectional"))
      (node (ref "U3") (pin "P18") (pinfunction "INT1_G_P18") (pintype "output"))
    )
    (net (code "18") (name "LSM330_INT2_ACCL") (class "Default")
      (node (ref "U1") (pin "38") (pinfunction "PORTC_7_38") (pintype "bidirectional"))
      (node (ref "U3") (pin "P19") (pinfunction "INT2_A_P19") (pintype "output"))
    )
    (net (code "19") (name "MPL311_P_INT1") (class "Default")
      (node (ref "U1") (pin "39") (pinfunction "PORTC_8_39") (pintype "bidirectional"))
      (node (ref "U4") (pin "P6") (pinfunction "INT1_P6") (pintype "output"))
    )
    (net (code "20") (name "MPL311_P_INT2") (class "Default")
      (node (ref "U1") (pin "40") (pinfunction "PORTC_9_40") (pintype "bidirectional"))
      (node (ref "U4") (pin "P5") (pinfunction "INT2_P5") (pintype "output"))
    )
    (net (code "21") (name "Net-(U1A-VCAP_1)") (class "Default")
      (node (ref "C2") (pin "1") (pinfunction "1_1") (pintype "passive"))
      (node (ref "U1") (pin "31") (pinfunction "VCAP_1_31") (pintype "bidirectional"))
    )
    (net (code "22") (name "Net-(U1A-VCAP_2)") (class "Default")
      (node (ref "C1") (pin "1") (pinfunction "1_1") (pintype "passive"))
      (node (ref "U1") (pin "47") (pinfunction "VCAP_2_47") (pintype "bidirectional"))
    )
    (net (code "23") (name "Net-(U1E-PORTH_0)") (class "Default")
      (node (ref "C8") (pin "1") (pinfunction "1_1") (pintype "passive"))
      (node (ref "U1") (pin "5") (pinfunction "PORTH_0_5") (pintype "bidirectional"))
      (node (ref "XTAL1") (pin "P$1") (pinfunction "Q1_P$1") (pintype "bidirectional"))
    )
    (net (code "24") (name "Net-(U1E-PORTH_1)") (class "Default")
      (node (ref "C7") (pin "1") (pinfunction "1_1") (pintype "passive"))
      (node (ref "U1") (pin "6") (pinfunction "PORTH_1_6") (pintype "bidirectional"))
      (node (ref "XTAL1") (pin "P$3") (pinfunction "Q2_P$3") (pintype "bidirectional"))
    )
    (net (code "25") (name "Net-(U2-C1)") (class "Default")
      (node (ref "C10") (pin "1") (pinfunction "1_1") (pintype "passive"))
      (node (ref "U2") (pin "P6") (pinfunction "C1_P6") (pintype "bidirectional"))
    )
    (net (code "26") (name "Net-(U2-SETC)") (class "Default")
      (node (ref "C12") (pin "2") (pinfunction "2_2") (pintype "passive"))
      (node (ref "U2") (pin "P13") (pinfunction "SETC_P13") (pintype "bidirectional"))
    )
    (net (code "27") (name "Net-(U2-SETP)") (class "Default")
      (node (ref "C12") (pin "1") (pinfunction "1_1") (pintype "passive"))
      (node (ref "U2") (pin "P12") (pinfunction "SETP_P12") (pintype "bidirectional"))
    )
    (net (code "28") (name "Net-(U3-CAP)") (class "Default")
      (node (ref "C13") (pin "1") (pinfunction "1_1") (pintype "passive"))
      (node (ref "U3") (pin "P15") (pinfunction "CAP_P15") (pintype "power_in"))
    )
    (net (code "29") (name "Net-(U4-CAP)") (class "Default")
      (node (ref "C16") (pin "1") (pinfunction "1_1") (pintype "passive"))
      (node (ref "U4") (pin "P2") (pinfunction "CAP_P2") (pintype "power_in"))
    )
    (net (code "30") (name "Net-(U5-RXD)") (class "Default")
      (node (ref "R4") (pin "1") (pinfunction "1_1") (pintype "passive"))
      (node (ref "U5") (pin "P10") (pinfunction "RXD_P10") (pintype "bidirectional"))
    )
    (net (code "31") (name "Net-(U5-TXD)") (class "Default")
      (node (ref "R3") (pin "1") (pinfunction "1_1") (pintype "passive"))
      (node (ref "U5") (pin "P9") (pinfunction "TXD_P9") (pintype "bidirectional"))
    )
    (net (code "32") (name "Net-(U5-VBACKUP)") (class "Default")
      (node (ref "C18") (pin "1") (pinfunction "1_1") (pintype "passive"))
      (node (ref "U5") (pin "P4") (pinfunction "VBACKUP_P4") (pintype "bidirectional"))
    )
    (net (code "33") (name "PB8") (class "Default")
      (node (ref "R5") (pin "1") (pinfunction "1_1") (pintype "passive"))
      (node (ref "U1") (pin "61") (pinfunction "PORTB_8_61") (pintype "bidirectional"))
    )
    (net (code "34") (name "PB9") (class "Default")
      (node (ref "R6") (pin "1") (pinfunction "1_1") (pintype "passive"))
      (node (ref "U1") (pin "62") (pinfunction "PORTB_9_62") (pintype "bidirectional"))
    )
    (net (code "35") (name "SPIEXT_CLK") (class "Default")
      (node (ref "P4") (pin "P$1") (pinfunction "CLK_P$1") (pintype "bidirectional"))
      (node (ref "U1") (pin "34") (pinfunction "PORTB_13_34") (pintype "bidirectional"))
    )
    (net (code "36") (name "SPIEXT_MISO") (class "Default")
      (node (ref "P4") (pin "P$3") (pinfunction "MISO_P$3") (pintype "bidirectional"))
      (node (ref "U1") (pin "35") (pinfunction "PORTB_14_35") (pintype "bidirectional"))
    )
    (net (code "37") (name "SPIEXT_MOSI") (class "Default")
      (node (ref "P4") (pin "P$2") (pinfunction "MOSI_P$2") (pintype "bidirectional"))
      (node (ref "U1") (pin "36") (pinfunction "PORTB_15_36") (pintype "bidirectional"))
    )
    (net (code "38") (name "SPIEXT_NSS") (class "Default")
      (node (ref "P4") (pin "P$4") (pinfunction "NSS_P$4") (pintype "bidirectional"))
      (node (ref "U1") (pin "33") (pinfunction "PORTB_12_33") (pintype "bidirectional"))
    )
    (net (code "39") (name "SPI_CLK") (class "Default")
      (node (ref "U1") (pin "21") (pinfunction "PORTA_5_21") (pintype "bidirectional"))
      (node (ref "U3") (pin "P24") (pinfunction "SCL_P24") (pintype "input"))
    )
    (net (code "40") (name "SPI_CS_ACCL") (class "Default")
      (node (ref "U1") (pin "14") (pinfunction "PORTA_0_14") (pintype "bidirectional"))
      (node (ref "U3") (pin "P23") (pinfunction "~{CS_A}_P23") (pintype "input"))
    )
    (net (code "41") (name "SPI_CS_GYRO") (class "Default")
      (node (ref "U1") (pin "15") (pinfunction "PORTA_1_15") (pintype "bidirectional"))
      (node (ref "U3") (pin "P22") (pinfunction "~{CS_G}_P22") (pintype "input"))
    )
    (net (code "42") (name "SPI_MISO") (class "Default")
      (node (ref "U1") (pin "22") (pinfunction "PORTA_6_22") (pintype "bidirectional"))
      (node (ref "U3") (pin "P26") (pinfunction "SDO_G_P26") (pintype "output"))
      (node (ref "U3") (pin "P27") (pinfunction "SDO_A_P27") (pintype "output"))
    )
    (net (code "43") (name "SPI_MOSI") (class "Default")
      (node (ref "U1") (pin "23") (pinfunction "PORTA_7_23") (pintype "bidirectional"))
      (node (ref "U3") (pin "P28") (pinfunction "SDA_P28") (pintype "input"))
    )
    (net (code "44") (name "SWCLK") (class "Default")
      (node (ref "P2") (pin "P$2") (pinfunction "SWCLK_P$2") (pintype "bidirectional"))
      (node (ref "U1") (pin "49") (pinfunction "PORTA_14_49") (pintype "bidirectional"))
    )
    (net (code "45") (name "SWDIO") (class "Default")
      (node (ref "P2") (pin "P$4") (pinfunction "SWDIO_P$4") (pintype "bidirectional"))
      (node (ref "U1") (pin "46") (pinfunction "PORTA_13_46") (pintype "bidirectional"))
    )
    (net (code "46") (name "VDD") (class "Default")
      (node (ref "BOOT") (pin "P1") (pinfunction "P$1_P1") (pintype "bidirectional"))
      (node (ref "BOOT") (pin "P2") (pinfunction "P$1_P2") (pintype "bidirectional"))
      (node (ref "C11") (pin "1") (pinfunction "1_1") (pintype "passive"))
      (node (ref "C14") (pin "1") (pinfunction "1_1") (pintype "passive"))
      (node (ref "C15") (pin "1") (pinfunction "1_1") (pintype "passive"))
      (node (ref "C17") (pin "1") (pinfunction "1_1") (pintype "passive"))
      (node (ref "C22") (pin "1") (pinfunction "1_1") (pintype "passive"))
      (node (ref "C3") (pin "1") (pinfunction "1_1") (pintype "passive"))
      (node (ref "C4") (pin "1") (pinfunction "1_1") (pintype "passive"))
      (node (ref "C5") (pin "1") (pinfunction "1_1") (pintype "passive"))
      (node (ref "C6") (pin "1") (pinfunction "1_1") (pintype "passive"))
      (node (ref "L1") (pin "1") (pinfunction "1_1") (pintype "passive"))
      (node (ref "P2") (pin "P$1") (pinfunction "VDD_T_P$1") (pintype "bidirectional"))
      (node (ref "P3") (pin "P$3") (pinfunction "VDD_3P3V_P$3") (pintype "bidirectional"))
      (node (ref "R1") (pin "2") (pinfunction "2_2") (pintype "passive"))
      (node (ref "R7") (pin "2") (pinfunction "2_2") (pintype "passive"))
      (node (ref "R8") (pin "2") (pinfunction "2_2") (pintype "passive"))
      (node (ref "U1") (pin "1") (pinfunction "VBAT_1") (pintype "bidirectional"))
      (node (ref "U1") (pin "13") (pinfunction "VDDA_13") (pintype "bidirectional"))
      (node (ref "U1") (pin "19") (pinfunction "VDD_19") (pintype "bidirectional"))
      (node (ref "U1") (pin "32") (pinfunction "VDD_32") (pintype "bidirectional"))
      (node (ref "U1") (pin "48") (pinfunction "VDD_48") (pintype "bidirectional"))
      (node (ref "U1") (pin "64") (pinfunction "VDD_64") (pintype "bidirectional"))
      (node (ref "U2") (pin "P1") (pinfunction "VDD_IO_P1") (pintype "bidirectional"))
      (node (ref "U2") (pin "P14") (pinfunction "VDD_P14") (pintype "bidirectional"))
      (node (ref "U3") (pin "P10") (pinfunction "VDD_P10") (pintype "power_in"))
      (node (ref "U3") (pin "P11") (pinfunction "VDD_P11") (pintype "power_in"))
      (node (ref "U3") (pin "P12") (pinfunction "VDD_P12") (pintype "power_in"))
      (node (ref "U3") (pin "P13") (pinfunction "VDD_P13") (pintype "power_in"))
      (node (ref "U3") (pin "P14") (pinfunction "VDD_P14") (pintype "power_in"))
      (node (ref "U3") (pin "P21") (pinfunction "VDD_IO_P21") (pintype "power_in"))
      (node (ref "U3") (pin "P25") (pinfunction "VDD_IO_P25") (pintype "power_in"))
      (node (ref "U3") (pin "P7") (pinfunction "VDD_P7") (pintype "power_in"))
      (node (ref "U3") (pin "P8") (pinfunction "VDD_P8") (pintype "power_in"))
      (node (ref "U3") (pin "P9") (pinfunction "VDD_P9") (pintype "power_in"))
      (node (ref "U4") (pin "P1") (pinfunction "VDD_P1") (pintype "power_in"))
      (node (ref "U4") (pin "P4") (pinfunction "VDD_IO_P4") (pintype "power_in"))
      (node (ref "U6") (pin "3") (pinfunction "OUT_3") (pintype "bidirectional"))
    )
    (net (code "47") (name "VDD_5") (class "Default")
      (node (ref "C21") (pin "1") (pinfunction "1_1") (pintype "passive"))
      (node (ref "P1") (pin "P1") (pinfunction "1_P1") (pintype "passive"))
      (node (ref "P3") (pin "P$2") (pinfunction "VDD_5P0V_P$2") (pintype "bidirectional"))
      (node (ref "U1") (pin "42") (pinfunction "PORTA_9_42") (pintype "bidirectional"))
      (node (ref "U6") (pin "1") (pinfunction "IN_1") (pintype "bidirectional"))
    )
    (net (code "48") (name "VDD_GPS") (class "Default")
      (node (ref "C19") (pin "1") (pinfunction "1_1") (pintype "passive"))
      (node (ref "C20") (pin "1") (pinfunction "1_1") (pintype "passive"))
      (node (ref "L1") (pin "2") (pinfunction "2_2") (pintype "passive"))
      (node (ref "U5") (pin "P1") (pinfunction "VDD_P1") (pintype "bidirectional"))
    )
    (net (code "49") (name "unconnected-(P1-4-PadP4)") (class "Default")
      (node (ref "P1") (pin "P4") (pinfunction "4_P4") (pintype "passive"))
    )
    (net (code "50") (name "unconnected-(U1B-PORTA_4-Pad20)") (class "Default")
      (node (ref "U1") (pin "20") (pinfunction "PORTA_4_20") (pintype "bidirectional"))
    )
    (net (code "51") (name "unconnected-(U1B-PORTA_8-Pad41)") (class "Default")
      (node (ref "U1") (pin "41") (pinfunction "PORTA_8_41") (pintype "bidirectional"))
    )
    (net (code "52") (name "unconnected-(U1B-PORTA_10-Pad43)") (class "Default")
      (node (ref "U1") (pin "43") (pinfunction "PORTA_10_43") (pintype "bidirectional"))
    )
    (net (code "53") (name "unconnected-(U1B-PORTA_15-Pad50)") (class "Default")
      (node (ref "U1") (pin "50") (pinfunction "PORTA_15_50") (pintype "bidirectional"))
    )
    (net (code "54") (name "unconnected-(U1C-PORTB_0-Pad26)") (class "Default")
      (node (ref "U1") (pin "26") (pinfunction "PORTB_0_26") (pintype "bidirectional"))
    )
    (net (code "55") (name "unconnected-(U1C-PORTB_1-Pad27)") (class "Default")
      (node (ref "U1") (pin "27") (pinfunction "PORTB_1_27") (pintype "bidirectional"))
    )
    (net (code "56") (name "unconnected-(U1C-PORTB_3-Pad55)") (class "Default")
      (node (ref "U1") (pin "55") (pinfunction "PORTB_3_55") (pintype "bidirectional"))
    )
    (net (code "57") (name "unconnected-(U1C-PORTB_4-Pad56)") (class "Default")
      (node (ref "U1") (pin "56") (pinfunction "PORTB_4_56") (pintype "bidirectional"))
    )
    (net (code "58") (name "unconnected-(U1C-PORTB_5-Pad57)") (class "Default")
      (node (ref "U1") (pin "57") (pinfunction "PORTB_5_57") (pintype "bidirectional"))
    )
    (net (code "59") (name "unconnected-(U1C-PORTB_6-Pad58)") (class "Default")
      (node (ref "U1") (pin "58") (pinfunction "PORTB_6_58") (pintype "bidirectional"))
    )
    (net (code "60") (name "unconnected-(U1C-PORTB_7-Pad59)") (class "Default")
      (node (ref "U1") (pin "59") (pinfunction "PORTB_7_59") (pintype "bidirectional"))
    )
    (net (code "61") (name "unconnected-(U1C-PORTB_10-Pad29)") (class "Default")
      (node (ref "U1") (pin "29") (pinfunction "PORTB_10_29") (pintype "bidirectional"))
    )
    (net (code "62") (name "unconnected-(U1C-PORTB_11-Pad30)") (class "Default")
      (node (ref "U1") (pin "30") (pinfunction "PORTB_11_30") (pintype "bidirectional"))
    )
    (net (code "63") (name "unconnected-(U1D-PORTC_12-Pad53)") (class "Default")
      (node (ref "U1") (pin "53") (pinfunction "PORTC_12_53") (pintype "bidirectional"))
    )
    (net (code "64") (name "unconnected-(U1D-PORTC_13-Pad2)") (class "Default")
      (node (ref "U1") (pin "2") (pinfunction "PORTC_13_2") (pintype "bidirectional"))
    )
    (net (code "65") (name "unconnected-(U1D-PORTC_14-Pad3)") (class "Default")
      (node (ref "U1") (pin "3") (pinfunction "PORTC_14_3") (pintype "bidirectional"))
    )
    (net (code "66") (name "unconnected-(U1D-PORTC_15-Pad4)") (class "Default")
      (node (ref "U1") (pin "4") (pinfunction "PORTC_15_4") (pintype "bidirectional"))
    )
    (net (code "67") (name "unconnected-(U1E-PORTD_2-Pad54)") (class "Default")
      (node (ref "U1") (pin "54") (pinfunction "PORTD_2_54") (pintype "bidirectional"))
    )
    (net (code "68") (name "unconnected-(U5-DMINUS-PadP7)") (class "Default")
      (node (ref "U5") (pin "P7") (pinfunction "DMINUS_P7") (pintype "bidirectional"))
    )
    (net (code "69") (name "unconnected-(U5-DPLUS-PadP6)") (class "Default")
      (node (ref "U5") (pin "P6") (pinfunction "DPLUS_P6") (pintype "bidirectional"))
    )
    (net (code "70") (name "~{RST}") (class "Default")
      (node (ref "C9") (pin "1") (pinfunction "1_1") (pintype "passive"))
      (node (ref "P2") (pin "P$5") (pinfunction "~{RST}_P$5") (pintype "bidirectional"))
      (node (ref "R1") (pin "1") (pinfunction "1_1") (pintype "passive"))
      (node (ref "RST") (pin "P3") (pinfunction "P$2_P3") (pintype "bidirectional"))
      (node (ref "RST") (pin "P4") (pinfunction "P$2_P4") (pintype "bidirectional"))
      (node (ref "U1") (pin "7") (pinfunction "~{RST}_7") (pintype "bidirectional"))
    )
  )
)
